# SparkFun_Buck_Regulator_AP63357DV-7_Baby.net
KiCad netlist of a schematic drawn in EAGLE
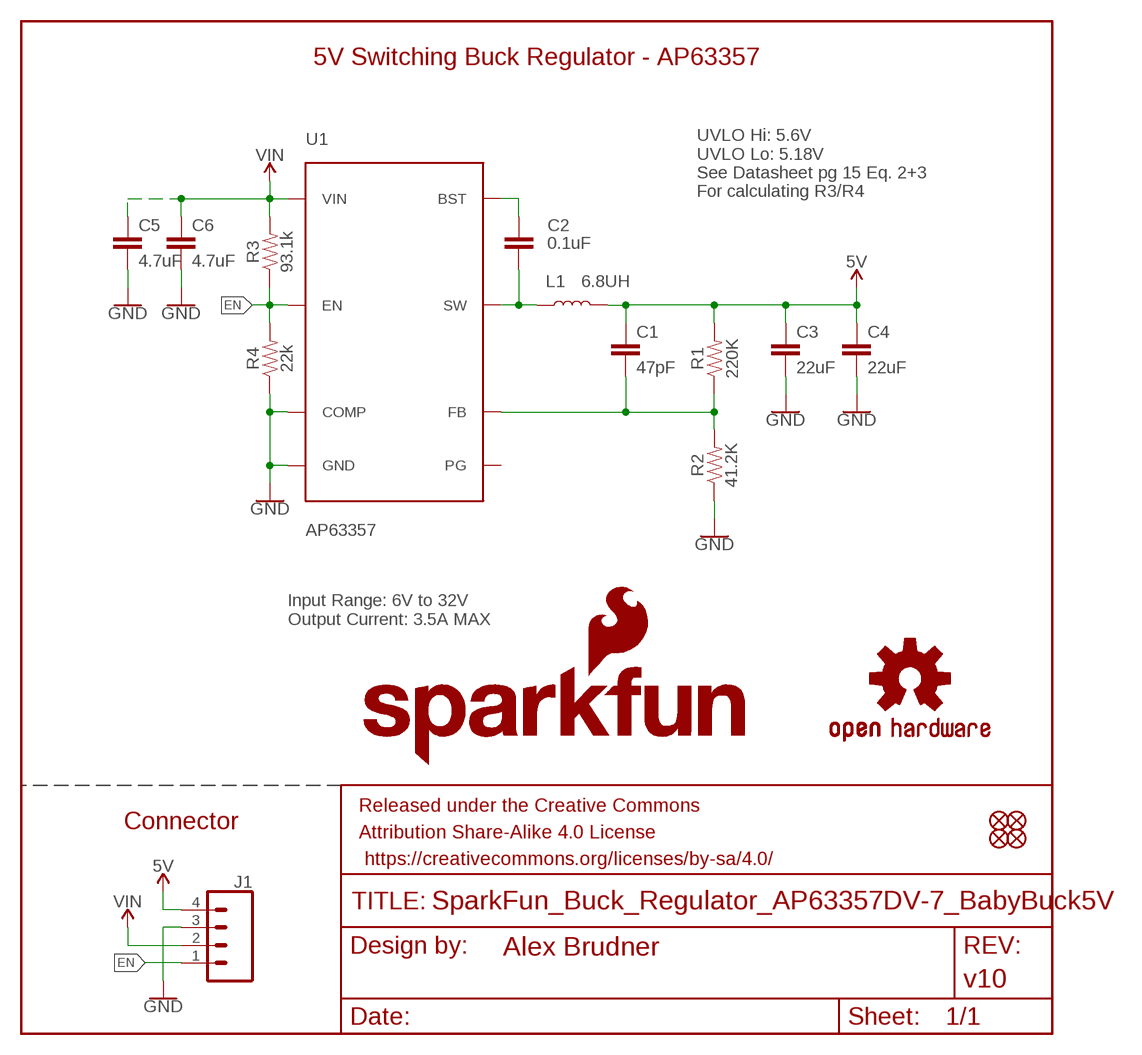
[diagram p0: schematic, sheet 1]

(export (version "E")
  (design (tool "Eeschema 10.0.6"))
  (components
    (comp (ref "C1")
      (value "47pF")
      (footprint "eagle-import:0402-TIGHT")
      (libsource (lib "eagle-import") (part "47PF-0402_TIGHT-25V-5%-X7R"))
    )
    (comp (ref "C2")
      (value "0.1uF")
      (footprint "eagle-import:0402-TIGHT")
      (libsource (lib "eagle-import") (part "0.1UF-0402T-16V-10%"))
    )
    (comp (ref "C3")
      (value "22uF")
      (footprint "eagle-import:0805")
      (libsource (lib "eagle-import") (part "22UF-0805-16V-20%"))
    )
    (comp (ref "C4")
      (value "22uF")
      (footprint "eagle-import:0805")
      (libsource (lib "eagle-import") (part "22UF-0805-16V-20%"))
    )
    (comp (ref "C5")
      (value "4.7uF")
      (footprint "eagle-import:0805")
      (libsource (lib "eagle-import") (part "4.7UF-0805-50V-(10%)"))
    )
    (comp (ref "C6")
      (value "4.7uF")
      (footprint "eagle-import:0805")
      (libsource (lib "eagle-import") (part "4.7UF-0805-50V-(10%)"))
    )
    (comp (ref "FD1")
      (value "FIDUCIALUFIDUCIAL")
      (footprint "eagle-import:FIDUCIAL-MICRO")
      (libsource (lib "eagle-import") (part "FIDUCIALUFIDUCIAL"))
    )
    (comp (ref "FD2")
      (value "FIDUCIALUFIDUCIAL")
      (footprint "eagle-import:FIDUCIAL-MICRO")
      (libsource (lib "eagle-import") (part "FIDUCIALUFIDUCIAL"))
    )
    (comp (ref "FD3")
      (value "FIDUCIALUFIDUCIAL")
      (footprint "eagle-import:FIDUCIAL-MICRO")
      (libsource (lib "eagle-import") (part "FIDUCIALUFIDUCIAL"))
    )
    (comp (ref "FD4")
      (value "FIDUCIALUFIDUCIAL")
      (footprint "eagle-import:FIDUCIAL-MICRO")
      (libsource (lib "eagle-import") (part "FIDUCIALUFIDUCIAL"))
    )
    (comp (ref "FRAME1")
      (value "FRAME-LEDGER")
      (footprint "eagle-import:CREATIVE_COMMONS")
      (fields (field (name "DESIGNER") "Alex Brudner") (field (name "REV") "v10"))
      (libsource (lib "eagle-import") (part "FRAME-LEDGER"))
    )
    (comp (ref "J1")
      (value "CONN_041X04_NO_SILK_NO_POP")
      (footprint "eagle-import:1X04_NO_SILK")
      (libsource (lib "eagle-import") (part "CONN_041X04_NO_SILK_NO_POP"))
    )
    (comp (ref "L1")
      (value "6.8UH")
      (footprint "eagle-import:07A7_6U8H")
      (libsource (lib "eagle-import") (part "6.8UH"))
    )
    (comp (ref "LOGO1")
      (value "SFE_LOGO_NAME_FLAMEBLANK")
      (footprint "eagle-import:BLANK")
      (libsource (lib "eagle-import") (part "SFE_LOGO_NAME_FLAMEBLANK"))
    )
    (comp (ref "LOGO2")
      (value "OSHW-LOGOMINI")
      (footprint "eagle-import:OSHW-LOGO-MINI")
      (libsource (lib "eagle-import") (part "OSHW-LOGOMINI"))
    )
    (comp (ref "R1")
      (value "220K")
      (footprint "eagle-import:0402-TIGHT")
      (fields (field (name "RES") "220K"))
      (libsource (lib "eagle-import") (part "220KOHM-0402T-1/16W-1%"))
    )
    (comp (ref "R2")
      (value "41.2K")
      (footprint "eagle-import:0402-TIGHT")
      (libsource (lib "eagle-import") (part "41.2KOHM-0402-1/16W-1%(41.2KOHM)"))
    )
    (comp (ref "R3")
      (value "93.1k")
      (footprint "eagle-import:0402-TIGHT")
      (libsource (lib "eagle-import") (part "93.1KOHM-0402-1/16W-1%(93.1KOHM)"))
    )
    (comp (ref "R4")
      (value "22k")
      (footprint "eagle-import:0402-TIGHT")
      (libsource (lib "eagle-import") (part "22KOHM-0402_TIGHT-1/10W-1%"))
    )
    (comp (ref "U1")
      (value "AP63357")
      (footprint "eagle-import:V-DFN3020-13")
      (libsource (lib "eagle-import") (part "AP63357"))
    )
  )
  (nets
    (net (code "1") (name "5V") (class "Default")
      (node (ref "C1") (pin "1") (pinfunction "1_1") (pintype "passive"))
      (node (ref "C3") (pin "1") (pinfunction "1_1") (pintype "passive"))
      (node (ref "C4") (pin "1") (pinfunction "1_1") (pintype "passive"))
      (node (ref "J1") (pin "4") (pinfunction "4_4") (pintype "passive"))
      (node (ref "L1") (pin "P$2") (pinfunction "2_P$2") (pintype "passive"))
      (node (ref "R1") (pin "2") (pinfunction "2_2") (pintype "passive"))
    )
    (net (code "2") (name "EN") (class "Default")
      (node (ref "J1") (pin "1") (pinfunction "1_1") (pintype "passive"))
      (node (ref "R3") (pin "1") (pinfunction "1_1") (pintype "passive"))
      (node (ref "R4") (pin "2") (pinfunction "2_2") (pintype "passive"))
      (node (ref "U1") (pin "P$2") (pinfunction "EN_P$2") (pintype "bidirectional"))
    )
    (net (code "3") (name "GND") (class "Default")
      (node (ref "C3") (pin "2") (pinfunction "2_2") (pintype "passive"))
      (node (ref "C4") (pin "2") (pinfunction "2_2") (pintype "passive"))
      (node (ref "C5") (pin "2") (pinfunction "2_2") (pintype "passive"))
      (node (ref "C6") (pin "2") (pinfunction "2_2") (pintype "passive"))
      (node (ref "J1") (pin "3") (pinfunction "3_3") (pintype "passive"))
      (node (ref "R2") (pin "1") (pinfunction "1_1") (pintype "passive"))
      (node (ref "R4") (pin "1") (pinfunction "1_1") (pintype "passive"))
      (node (ref "U1") (pin "P$4") (pinfunction "COMP_P$4") (pintype "bidirectional"))
      (node (ref "U1") (pin "P$8") (pinfunction "GND_P$8") (pintype "power_in"))
    )
    (net (code "4") (name "Net-(L1-1)") (class "Default")
      (node (ref "C2") (pin "2") (pinfunction "2_2") (pintype "passive"))
      (node (ref "L1") (pin "P$1") (pinfunction "1_P$1") (pintype "passive"))
      (node (ref "U1") (pin "P$7") (pinfunction "SW_P$7") (pintype "power_in"))
      (node (ref "U1") (pin "P$9") (pinfunction "SW_P$9") (pintype "power_in"))
    )
    (net (code "5") (name "Net-(U1-BST)") (class "Default")
      (node (ref "C2") (pin "1") (pinfunction "1_1") (pintype "passive"))
      (node (ref "U1") (pin "P$6") (pinfunction "BST_P$6") (pintype "bidirectional"))
    )
    (net (code "6") (name "Net-(U1-FB)") (class "Default")
      (node (ref "C1") (pin "2") (pinfunction "2_2") (pintype "passive"))
      (node (ref "R1") (pin "1") (pinfunction "1_1") (pintype "passive"))
      (node (ref "R2") (pin "2") (pinfunction "2_2") (pintype "passive"))
      (node (ref "U1") (pin "P$3") (pinfunction "FB_P$3") (pintype "input"))
    )
    (net (code "7") (name "VIN") (class "Default")
      (node (ref "C5") (pin "1") (pinfunction "1_1") (pintype "passive"))
      (node (ref "C6") (pin "1") (pinfunction "1_1") (pintype "passive"))
      (node (ref "J1") (pin "2") (pinfunction "2_2") (pintype "passive"))
      (node (ref "R3") (pin "2") (pinfunction "2_2") (pintype "passive"))
      (node (ref "U1") (pin "P$1") (pinfunction "VIN_P$1") (pintype "power_in"))
    )
    (net (code "8") (name "unconnected-(U1-PG-PadP$5)") (class "Default")
      (node (ref "U1") (pin "P$5") (pinfunction "PG_P$5") (pintype "output"))
    )
  )
)
